# tempShield.net
KiCad netlist of a schematic drawn in EAGLE
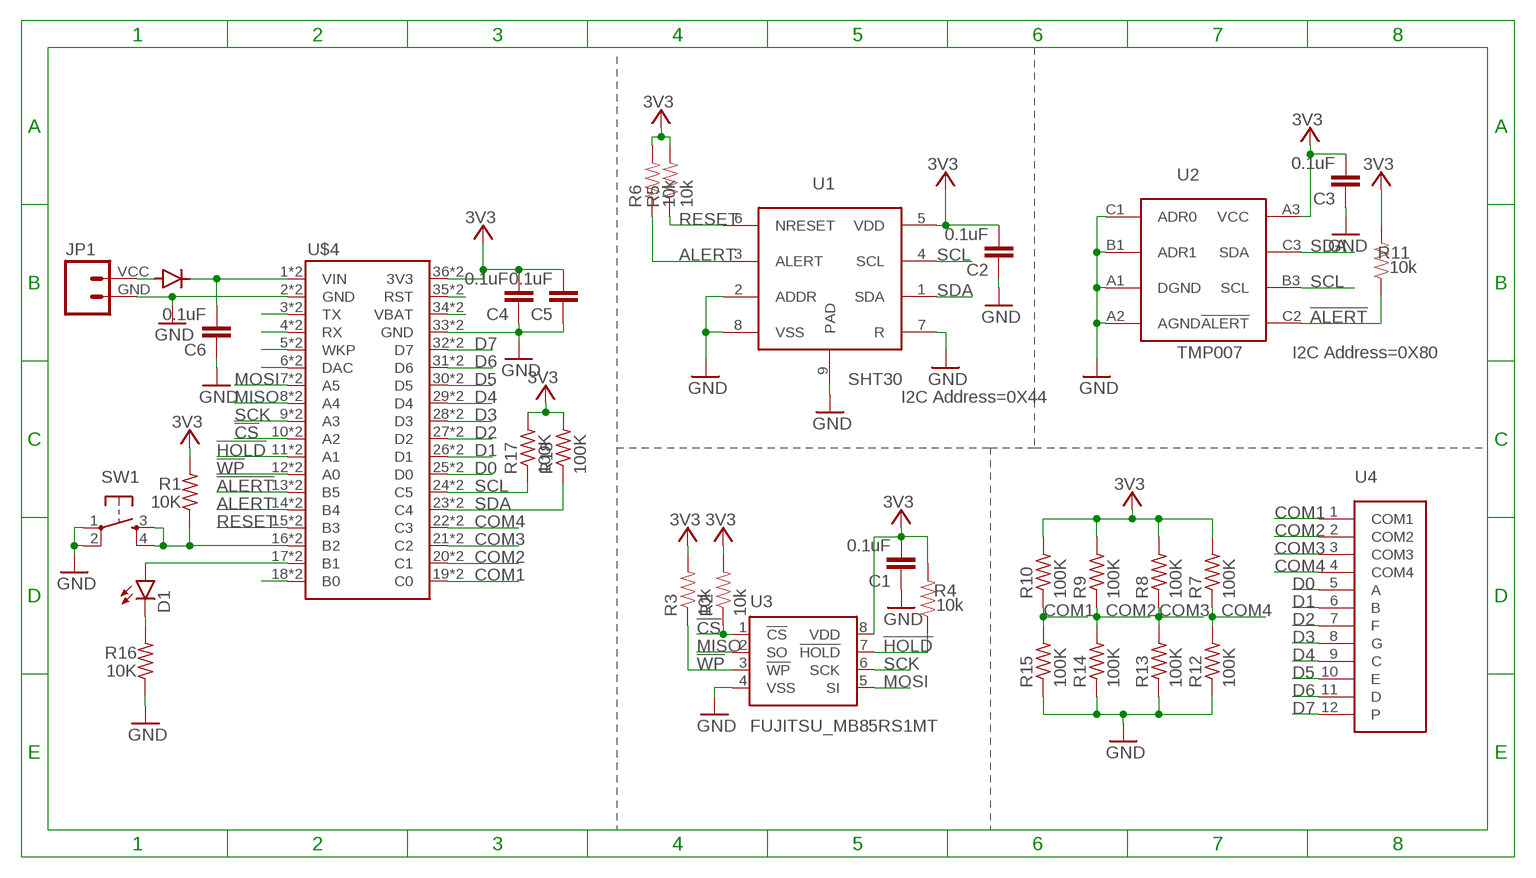
[diagram p0: schematic, sheet 1]

(export (version "E")
  (design (tool "Eeschema 10.0.6"))
  (components
    (comp (ref "C1")
      (value "0.1uF")
      (footprint "eagle-import:0603-CAP")
      (libsource (lib "eagle-import") (part "0.22UF50V-20%,+80%(0603)"))
    )
    (comp (ref "C2")
      (value "0.1uF")
      (footprint "eagle-import:0603-CAP")
      (libsource (lib "eagle-import") (part "0.22UF50V-20%,+80%(0603)"))
    )
    (comp (ref "C3")
      (value "0.1uF")
      (footprint "eagle-import:0603-CAP")
      (libsource (lib "eagle-import") (part "0.22UF50V-20%,+80%(0603)"))
    )
    (comp (ref "C4")
      (value "0.1uF")
      (footprint "eagle-import:0603-CAP")
      (libsource (lib "eagle-import") (part "0.22UF50V-20%,+80%(0603)"))
    )
    (comp (ref "C5")
      (value "0.1uF")
      (footprint "eagle-import:0603-CAP")
      (libsource (lib "eagle-import") (part "0.22UF50V-20%,+80%(0603)"))
    )
    (comp (ref "C6")
      (value "0.1uF")
      (footprint "eagle-import:0603-CAP")
      (libsource (lib "eagle-import") (part "0.22UF50V-20%,+80%(0603)"))
    )
    (comp (ref "D1")
      (value "LED0603")
      (footprint "eagle-import:LED-0603")
      (libsource (lib "eagle-import") (part "LED0603"))
    )
    (comp (ref "JP1")
      (value "SPARKFUN-CONNECTORS_M024UCON-15767")
      (footprint "eagle-import:SPARKFUN-CONNECTORS_JST-2-SMD-VERT")
      (libsource (lib "eagle-import") (part "SPARKFUN-CONNECTORS_M024UCON-15767"))
    )
    (comp (ref "R1")
      (value "10K")
      (footprint "eagle-import:R0402")
      (libsource (lib "eagle-import") (part "R-US_R0402"))
    )
    (comp (ref "R2")
      (value "10k")
      (footprint "eagle-import:0603-RES")
      (libsource (lib "eagle-import") (part "0.27OHM-1/10W-1%(0603)"))
    )
    (comp (ref "R3")
      (value "10k")
      (footprint "eagle-import:0603-RES")
      (libsource (lib "eagle-import") (part "0.27OHM-1/10W-1%(0603)"))
    )
    (comp (ref "R4")
      (value "10k")
      (footprint "eagle-import:0603-RES")
      (libsource (lib "eagle-import") (part "0.27OHM-1/10W-1%(0603)"))
    )
    (comp (ref "R5")
      (value "10k")
      (footprint "eagle-import:0603-RES")
      (libsource (lib "eagle-import") (part "0.27OHM-1/10W-1%(0603)"))
    )
    (comp (ref "R6")
      (value "10k")
      (footprint "eagle-import:0603-RES")
      (libsource (lib "eagle-import") (part "0.27OHM-1/10W-1%(0603)"))
    )
    (comp (ref "R7")
      (value "100K")
      (footprint "eagle-import:R0402")
      (libsource (lib "eagle-import") (part "R-US_R0402"))
    )
    (comp (ref "R8")
      (value "100K")
      (footprint "eagle-import:R0402")
      (libsource (lib "eagle-import") (part "R-US_R0402"))
    )
    (comp (ref "R9")
      (value "100K")
      (footprint "eagle-import:R0402")
      (libsource (lib "eagle-import") (part "R-US_R0402"))
    )
    (comp (ref "R10")
      (value "100K")
      (footprint "eagle-import:R0402")
      (libsource (lib "eagle-import") (part "R-US_R0402"))
    )
    (comp (ref "R11")
      (value "10k")
      (footprint "eagle-import:0603-RES")
      (libsource (lib "eagle-import") (part "0.27OHM-1/10W-1%(0603)"))
    )
    (comp (ref "R12")
      (value "100K")
      (footprint "eagle-import:R0402")
      (libsource (lib "eagle-import") (part "R-US_R0402"))
    )
    (comp (ref "R13")
      (value "100K")
      (footprint "eagle-import:R0402")
      (libsource (lib "eagle-import") (part "R-US_R0402"))
    )
    (comp (ref "R14")
      (value "100K")
      (footprint "eagle-import:R0402")
      (libsource (lib "eagle-import") (part "R-US_R0402"))
    )
    (comp (ref "R15")
      (value "100K")
      (footprint "eagle-import:R0402")
      (libsource (lib "eagle-import") (part "R-US_R0402"))
    )
    (comp (ref "R16")
      (value "10K")
      (footprint "eagle-import:R0402")
      (libsource (lib "eagle-import") (part "R-US_R0402"))
    )
    (comp (ref "R17")
      (value "100K")
      (footprint "eagle-import:R0402")
      (libsource (lib "eagle-import") (part "R-US_R0402"))
    )
    (comp (ref "R18")
      (value "100K")
      (footprint "eagle-import:R0402")
      (libsource (lib "eagle-import") (part "R-US_R0402"))
    )
    (comp (ref "SW1")
      (value "SWITCH_SPST_4_PIN")
      (footprint "eagle-import:TACTILE-SWITCH-SMD")
      (libsource (lib "eagle-import") (part "SWITCH_SPST_4_PIN"))
    )
    (comp (ref "U$1")
      (value "PARTICLE_DIODE_NT")
      (footprint "eagle-import:PARTICLE_DIODE-DO-220AA_NT(SMP)")
      (libsource (lib "eagle-import") (part "PARTICLE_DIODE_NT"))
    )
    (comp (ref "U$4")
      (value "MICROBUILDER_ELECTRON_SMT")
      (footprint "eagle-import:MICROBUILDER_ELECTRON_SMT")
      (libsource (lib "eagle-import") (part "MICROBUILDER_ELECTRON_SMT"))
    )
    (comp (ref "U1")
      (value "SHT30")
      (footprint "eagle-import:SHT30")
      (libsource (lib "eagle-import") (part "SHT30SHT30"))
    )
    (comp (ref "U2")
      (value "TMP007")
      (footprint "eagle-import:TMP007_1")
      (libsource (lib "eagle-import") (part "TMP007"))
    )
    (comp (ref "U3")
      (value "FUJITSU_MB85RS1MT")
      (footprint "eagle-import:FUJITSU_SO08")
      (libsource (lib "eagle-import") (part "FUJITSU_MB85RS1MT"))
    )
    (comp (ref "U4")
      (value "LCD")
      (footprint "eagle-import:LCD")
      (libsource (lib "eagle-import") (part "LCD"))
    )
  )
  (nets
    (net (code "1") (name "/ALERT") (class "Default")
      (node (ref "R6") (pin "1") (pinfunction "1_1") (pintype "passive"))
      (node (ref "U$4") (pin "14") (pinfunction "B4_14") (pintype "bidirectional"))
      (node (ref "U$4") (pin "14B") (pinfunction "B4_14B") (pintype "bidirectional"))
      (node (ref "U1") (pin "3") (pinfunction "ALERT_3") (pintype "bidirectional"))
    )
    (net (code "2") (name "/COM1") (class "Default")
      (node (ref "R10") (pin "1") (pinfunction "1_1") (pintype "passive"))
      (node (ref "R15") (pin "2") (pinfunction "2_2") (pintype "passive"))
      (node (ref "U$4") (pin "19") (pinfunction "C0_19") (pintype "bidirectional"))
      (node (ref "U$4") (pin "19B") (pinfunction "C0_19B") (pintype "bidirectional"))
      (node (ref "U4") (pin "1") (pinfunction "COM1_1") (pintype "bidirectional"))
    )
    (net (code "3") (name "/COM2") (class "Default")
      (node (ref "R14") (pin "2") (pinfunction "2_2") (pintype "passive"))
      (node (ref "R9") (pin "1") (pinfunction "1_1") (pintype "passive"))
      (node (ref "U$4") (pin "20") (pinfunction "C1_20") (pintype "bidirectional"))
      (node (ref "U$4") (pin "20B") (pinfunction "C1_20B") (pintype "bidirectional"))
      (node (ref "U4") (pin "2") (pinfunction "COM2_2") (pintype "bidirectional"))
    )
    (net (code "4") (name "/COM3") (class "Default")
      (node (ref "R13") (pin "2") (pinfunction "2_2") (pintype "passive"))
      (node (ref "R8") (pin "1") (pinfunction "1_1") (pintype "passive"))
      (node (ref "U$4") (pin "21") (pinfunction "C2_21") (pintype "bidirectional"))
      (node (ref "U$4") (pin "21B") (pinfunction "C2_21B") (pintype "bidirectional"))
      (node (ref "U4") (pin "3") (pinfunction "COM3_3") (pintype "bidirectional"))
    )
    (net (code "5") (name "/COM4") (class "Default")
      (node (ref "R12") (pin "2") (pinfunction "2_2") (pintype "passive"))
      (node (ref "R7") (pin "1") (pinfunction "1_1") (pintype "passive"))
      (node (ref "U$4") (pin "22") (pinfunction "C3_22") (pintype "bidirectional"))
      (node (ref "U$4") (pin "22B") (pinfunction "C3_22B") (pintype "bidirectional"))
      (node (ref "U4") (pin "4") (pinfunction "COM4_4") (pintype "bidirectional"))
    )
    (net (code "6") (name "/D0") (class "Default")
      (node (ref "U$4") (pin "25") (pinfunction "D0_25") (pintype "bidirectional"))
      (node (ref "U$4") (pin "25B") (pinfunction "D0_25B") (pintype "bidirectional"))
      (node (ref "U4") (pin "5") (pinfunction "A_5") (pintype "bidirectional"))
    )
    (net (code "7") (name "/D1") (class "Default")
      (node (ref "U$4") (pin "26") (pinfunction "D1_26") (pintype "bidirectional"))
      (node (ref "U$4") (pin "26B") (pinfunction "D1_26B") (pintype "bidirectional"))
      (node (ref "U4") (pin "6") (pinfunction "B_6") (pintype "bidirectional"))
    )
    (net (code "8") (name "/D2") (class "Default")
      (node (ref "U$4") (pin "27") (pinfunction "D2_27") (pintype "bidirectional"))
      (node (ref "U$4") (pin "27B") (pinfunction "D2_27B") (pintype "bidirectional"))
      (node (ref "U4") (pin "7") (pinfunction "F_7") (pintype "bidirectional"))
    )
    (net (code "9") (name "/D3") (class "Default")
      (node (ref "U$4") (pin "28") (pinfunction "D3_28") (pintype "bidirectional"))
      (node (ref "U$4") (pin "28B") (pinfunction "D3_28B") (pintype "bidirectional"))
      (node (ref "U4") (pin "8") (pinfunction "G_8") (pintype "bidirectional"))
    )
    (net (code "10") (name "/D4") (class "Default")
      (node (ref "U$4") (pin "29") (pinfunction "D4_29") (pintype "bidirectional"))
      (node (ref "U$4") (pin "29B") (pinfunction "D4_29B") (pintype "bidirectional"))
      (node (ref "U4") (pin "9") (pinfunction "C_9") (pintype "bidirectional"))
    )
    (net (code "11") (name "/D5") (class "Default")
      (node (ref "U$4") (pin "30") (pinfunction "D5_30") (pintype "bidirectional"))
      (node (ref "U$4") (pin "30B") (pinfunction "D5_30B") (pintype "bidirectional"))
      (node (ref "U4") (pin "10") (pinfunction "E_10") (pintype "bidirectional"))
    )
    (net (code "12") (name "/D6") (class "Default")
      (node (ref "U$4") (pin "31") (pinfunction "D6_31") (pintype "bidirectional"))
      (node (ref "U$4") (pin "31B") (pinfunction "D6_31B") (pintype "bidirectional"))
      (node (ref "U4") (pin "11") (pinfunction "D_11") (pintype "bidirectional"))
    )
    (net (code "13") (name "/D7") (class "Default")
      (node (ref "U$4") (pin "32") (pinfunction "D7_32") (pintype "bidirectional"))
      (node (ref "U$4") (pin "32B") (pinfunction "D7_32B") (pintype "bidirectional"))
      (node (ref "U4") (pin "12") (pinfunction "P_12") (pintype "bidirectional"))
    )
    (net (code "14") (name "/MISO") (class "Default")
      (node (ref "U$4") (pin "8") (pinfunction "A4_8") (pintype "bidirectional"))
      (node (ref "U$4") (pin "8B") (pinfunction "A4_8B") (pintype "bidirectional"))
      (node (ref "U3") (pin "2") (pinfunction "SO_2") (pintype "output"))
    )
    (net (code "15") (name "/MOSI") (class "Default")
      (node (ref "U$4") (pin "7") (pinfunction "A5_7") (pintype "bidirectional"))
      (node (ref "U$4") (pin "7B") (pinfunction "A5_7B") (pintype "bidirectional"))
      (node (ref "U3") (pin "5") (pinfunction "SI_5") (pintype "output"))
    )
    (net (code "16") (name "/RESET") (class "Default")
      (node (ref "R5") (pin "1") (pinfunction "1_1") (pintype "passive"))
      (node (ref "U$4") (pin "15") (pinfunction "B3_15") (pintype "bidirectional"))
      (node (ref "U$4") (pin "15B") (pinfunction "B3_15B") (pintype "bidirectional"))
      (node (ref "U1") (pin "6") (pinfunction "NRESET_6") (pintype "bidirectional"))
    )
    (net (code "17") (name "/SCK") (class "Default")
      (node (ref "U$4") (pin "9") (pinfunction "A3_9") (pintype "bidirectional"))
      (node (ref "U$4") (pin "9B") (pinfunction "A3_9B") (pintype "bidirectional"))
      (node (ref "U3") (pin "6") (pinfunction "SCK_6") (pintype "input"))
    )
    (net (code "18") (name "/SCL") (class "Default")
      (node (ref "R17") (pin "1") (pinfunction "1_1") (pintype "passive"))
      (node (ref "U$4") (pin "24") (pinfunction "C5_24") (pintype "bidirectional"))
      (node (ref "U$4") (pin "24B") (pinfunction "C5_24B") (pintype "bidirectional"))
      (node (ref "U1") (pin "4") (pinfunction "SCL_4") (pintype "bidirectional"))
      (node (ref "U2") (pin "B3") (pinfunction "SCL_B3") (pintype "bidirectional"))
    )
    (net (code "19") (name "/SDA") (class "Default")
      (node (ref "R18") (pin "1") (pinfunction "1_1") (pintype "passive"))
      (node (ref "U$4") (pin "23") (pinfunction "C4_23") (pintype "bidirectional"))
      (node (ref "U$4") (pin "23B") (pinfunction "C4_23B") (pintype "bidirectional"))
      (node (ref "U1") (pin "1") (pinfunction "SDA_1") (pintype "bidirectional"))
      (node (ref "U2") (pin "C3") (pinfunction "SDA_C3") (pintype "bidirectional"))
    )
    (net (code "20") (name "/~{ALERT}") (class "Default")
      (node (ref "R11") (pin "1") (pinfunction "1_1") (pintype "passive"))
      (node (ref "U$4") (pin "13") (pinfunction "B5_13") (pintype "bidirectional"))
      (node (ref "U$4") (pin "13B") (pinfunction "B5_13B") (pintype "bidirectional"))
      (node (ref "U2") (pin "C2") (pinfunction "~{ALERT}_C2") (pintype "bidirectional"))
    )
    (net (code "21") (name "/~{CS}") (class "Default")
      (node (ref "R2") (pin "1") (pinfunction "1_1") (pintype "passive"))
      (node (ref "U$4") (pin "10") (pinfunction "A2_10") (pintype "bidirectional"))
      (node (ref "U$4") (pin "10B") (pinfunction "A2_10B") (pintype "bidirectional"))
      (node (ref "U3") (pin "1") (pinfunction "~{CS}_1") (pintype "output"))
    )
    (net (code "22") (name "/~{HOLD}") (class "Default")
      (node (ref "R4") (pin "1") (pinfunction "1_1") (pintype "passive"))
      (node (ref "U$4") (pin "11") (pinfunction "A1_11") (pintype "bidirectional"))
      (node (ref "U$4") (pin "11B") (pinfunction "A1_11B") (pintype "bidirectional"))
      (node (ref "U3") (pin "7") (pinfunction "~{HOLD}_7") (pintype "output"))
    )
    (net (code "23") (name "/~{WP}") (class "Default")
      (node (ref "R3") (pin "1") (pinfunction "1_1") (pintype "passive"))
      (node (ref "U$4") (pin "12") (pinfunction "A0_12") (pintype "bidirectional"))
      (node (ref "U$4") (pin "12B") (pinfunction "A0_12B") (pintype "bidirectional"))
      (node (ref "U3") (pin "3") (pinfunction "~{WP}_3") (pintype "input"))
    )
    (net (code "24") (name "3V3") (class "Default")
      (node (ref "C1") (pin "2") (pinfunction "2_2") (pintype "passive"))
      (node (ref "C2") (pin "2") (pinfunction "2_2") (pintype "passive"))
      (node (ref "C3") (pin "2") (pinfunction "2_2") (pintype "passive"))
      (node (ref "C4") (pin "2") (pinfunction "2_2") (pintype "passive"))
      (node (ref "C5") (pin "2") (pinfunction "2_2") (pintype "passive"))
      (node (ref "R1") (pin "2") (pinfunction "2_2") (pintype "passive"))
      (node (ref "R10") (pin "2") (pinfunction "2_2") (pintype "passive"))
      (node (ref "R11") (pin "2") (pinfunction "2_2") (pintype "passive"))
      (node (ref "R17") (pin "2") (pinfunction "2_2") (pintype "passive"))
      (node (ref "R18") (pin "2") (pinfunction "2_2") (pintype "passive"))
      (node (ref "R2") (pin "2") (pinfunction "2_2") (pintype "passive"))
      (node (ref "R3") (pin "2") (pinfunction "2_2") (pintype "passive"))
      (node (ref "R4") (pin "2") (pinfunction "2_2") (pintype "passive"))
      (node (ref "R5") (pin "2") (pinfunction "2_2") (pintype "passive"))
      (node (ref "R6") (pin "2") (pinfunction "2_2") (pintype "passive"))
      (node (ref "R7") (pin "2") (pinfunction "2_2") (pintype "passive"))
      (node (ref "R8") (pin "2") (pinfunction "2_2") (pintype "passive"))
      (node (ref "R9") (pin "2") (pinfunction "2_2") (pintype "passive"))
      (node (ref "U$4") (pin "36") (pinfunction "3V3_36") (pintype "power_in"))
      (node (ref "U$4") (pin "36B") (pinfunction "3V3_36B") (pintype "power_in"))
      (node (ref "U1") (pin "5") (pinfunction "VDD_5") (pintype "bidirectional"))
      (node (ref "U2") (pin "A3") (pinfunction "VCC_A3") (pintype "bidirectional"))
      (node (ref "U3") (pin "8") (pinfunction "VDD_8") (pintype "power_in"))
    )
    (net (code "25") (name "GND") (class "Default")
      (node (ref "C1") (pin "1") (pinfunction "1_1") (pintype "passive"))
      (node (ref "C2") (pin "1") (pinfunction "1_1") (pintype "passive"))
      (node (ref "C3") (pin "1") (pinfunction "1_1") (pintype "passive"))
      (node (ref "C4") (pin "1") (pinfunction "1_1") (pintype "passive"))
      (node (ref "C5") (pin "1") (pinfunction "1_1") (pintype "passive"))
      (node (ref "C6") (pin "1") (pinfunction "1_1") (pintype "passive"))
      (node (ref "JP1") (pin "GND") (pinfunction "1_GND") (pintype "passive"))
      (node (ref "R12") (pin "1") (pinfunction "1_1") (pintype "passive"))
      (node (ref "R13") (pin "1") (pinfunction "1_1") (pintype "passive"))
      (node (ref "R14") (pin "1") (pinfunction "1_1") (pintype "passive"))
      (node (ref "R15") (pin "1") (pinfunction "1_1") (pintype "passive"))
      (node (ref "R16") (pin "1") (pinfunction "1_1") (pintype "passive"))
      (node (ref "SW1") (pin "1") (pinfunction "1_1") (pintype "passive"))
      (node (ref "SW1") (pin "2") (pinfunction "2_2") (pintype "passive"))
      (node (ref "U$4") (pin "2") (pinfunction "GND_2") (pintype "power_in"))
      (node (ref "U$4") (pin "2B") (pinfunction "GND_2B") (pintype "power_in"))
      (node (ref "U$4") (pin "33") (pinfunction "GND_33") (pintype "power_in"))
      (node (ref "U$4") (pin "33B") (pinfunction "GND_33B") (pintype "power_in"))
      (node (ref "U1") (pin "2") (pinfunction "ADDR_2") (pintype "bidirectional"))
      (node (ref "U1") (pin "7") (pinfunction "R_7") (pintype "bidirectional"))
      (node (ref "U1") (pin "8") (pinfunction "VSS_8") (pintype "bidirectional"))
      (node (ref "U1") (pin "9") (pinfunction "PAD_9") (pintype "bidirectional"))
      (node (ref "U2") (pin "A1") (pinfunction "DGND_A1") (pintype "bidirectional"))
      (node (ref "U2") (pin "A2") (pinfunction "AGND_A2") (pintype "bidirectional"))
      (node (ref "U2") (pin "B1") (pinfunction "ADR1_B1") (pintype "bidirectional"))
      (node (ref "U2") (pin "C1") (pinfunction "ADR0_C1") (pintype "bidirectional"))
      (node (ref "U3") (pin "4") (pinfunction "VSS_4") (pintype "power_in"))
    )
    (net (code "26") (name "Net-(C6-Pad2)") (class "Default")
      (node (ref "C6") (pin "2") (pinfunction "2_2") (pintype "passive"))
      (node (ref "U$1") (pin "CATHODE") (pinfunction "CATHODE_CATHODE") (pintype "bidirectional"))
      (node (ref "U$4") (pin "1") (pinfunction "VIN_1") (pintype "power_in"))
      (node (ref "U$4") (pin "1B") (pinfunction "VIN_1B") (pintype "power_in"))
    )
    (net (code "27") (name "Net-(D1-PadA)") (class "Default")
      (node (ref "D1") (pin "A") (pinfunction "A_A") (pintype "passive"))
      (node (ref "U$4") (pin "17") (pinfunction "B1_17") (pintype "bidirectional"))
      (node (ref "U$4") (pin "17B") (pinfunction "B1_17B") (pintype "bidirectional"))
    )
    (net (code "28") (name "Net-(D1-PadC)") (class "Default")
      (node (ref "D1") (pin "C") (pinfunction "C_C") (pintype "passive"))
      (node (ref "R16") (pin "2") (pinfunction "2_2") (pintype "passive"))
    )
    (net (code "29") (name "Net-(JP1-2)") (class "Default")
      (node (ref "JP1") (pin "VCC") (pinfunction "2_VCC") (pintype "passive"))
      (node (ref "U$1") (pin "ANODE") (pinfunction "ANODE_ANODE") (pintype "bidirectional"))
    )
    (net (code "30") (name "Net-(R1-Pad1)") (class "Default")
      (node (ref "R1") (pin "1") (pinfunction "1_1") (pintype "passive"))
      (node (ref "SW1") (pin "3") (pinfunction "3_3") (pintype "passive"))
      (node (ref "SW1") (pin "4") (pinfunction "4_4") (pintype "passive"))
      (node (ref "U$4") (pin "16") (pinfunction "B2_16") (pintype "bidirectional"))
      (node (ref "U$4") (pin "16B") (pinfunction "B2_16B") (pintype "bidirectional"))
    )
    (net (code "31") (name "Net-(U$4-B0-Pad18)") (class "Default")
      (node (ref "U$4") (pin "18") (pinfunction "B0_18") (pintype "bidirectional"))
      (node (ref "U$4") (pin "18B") (pinfunction "B0_18B") (pintype "bidirectional"))
    )
    (net (code "32") (name "Net-(U$4-DAC-Pad6)") (class "Default")
      (node (ref "U$4") (pin "6") (pinfunction "DAC_6") (pintype "bidirectional"))
      (node (ref "U$4") (pin "6B") (pinfunction "DAC_6B") (pintype "bidirectional"))
    )
    (net (code "33") (name "Net-(U$4-RST-Pad35)") (class "Default")
      (node (ref "U$4") (pin "35") (pinfunction "RST_35") (pintype "bidirectional"))
      (node (ref "U$4") (pin "35B") (pinfunction "RST_35B") (pintype "bidirectional"))
    )
    (net (code "34") (name "Net-(U$4-RX-Pad4)") (class "Default")
      (node (ref "U$4") (pin "4") (pinfunction "RX_4") (pintype "bidirectional"))
      (node (ref "U$4") (pin "4B") (pinfunction "RX_4B") (pintype "bidirectional"))
    )
    (net (code "35") (name "Net-(U$4-TX-Pad3)") (class "Default")
      (node (ref "U$4") (pin "3") (pinfunction "TX_3") (pintype "bidirectional"))
      (node (ref "U$4") (pin "3B") (pinfunction "TX_3B") (pintype "bidirectional"))
    )
    (net (code "36") (name "Net-(U$4-VBAT-Pad34)") (class "Default")
      (node (ref "U$4") (pin "34") (pinfunction "VBAT_34") (pintype "passive"))
      (node (ref "U$4") (pin "34B") (pinfunction "VBAT_34B") (pintype "passive"))
    )
    (net (code "37") (name "Net-(U$4-WKP-Pad5)") (class "Default")
      (node (ref "U$4") (pin "5") (pinfunction "WKP_5") (pintype "bidirectional"))
      (node (ref "U$4") (pin "5B") (pinfunction "WKP_5B") (pintype "bidirectional"))
    )
  )
)
